# placa_carol.net
KiCad netlist of a schematic drawn in EAGLE
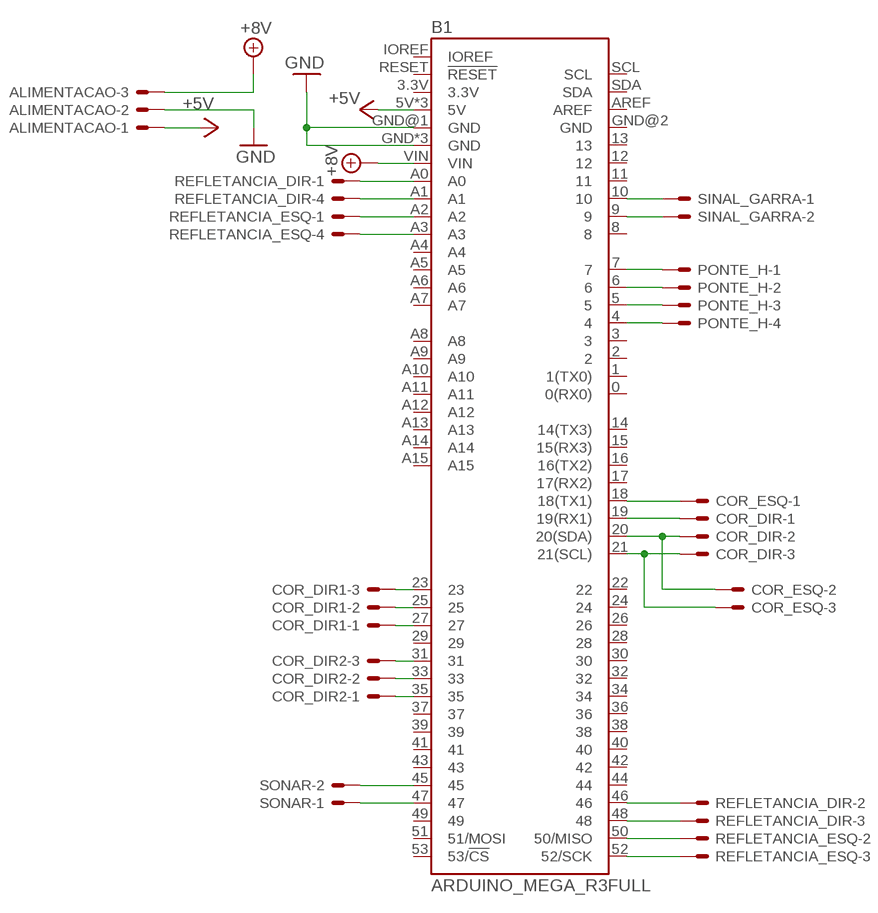
[diagram p0: schematic, sheet 1]

(export (version "E")
  (design (tool "Eeschema 10.0.6"))
  (components
    (comp (ref "ALIMENTACAO")
      (value "KK-156-3")
      (footprint "eagle-import:KK-156-3")
      (fields (field (name "MF") "MOLEX"))
      (libsource (lib "eagle-import") (part "KK-156-3"))
    )
    (comp (ref "B1")
      (value "ARDUINO_MEGA_R3FULL")
      (footprint "eagle-import:ARDUINO_MEGA_NO_SILK")
      (libsource (lib "eagle-import") (part "ARDUINO_MEGA_R3FULL"))
    )
    (comp (ref "COR_DIR")
      (value "JST-XH-03-PIN-LONG-PAD")
      (footprint "eagle-import:JST-XH-03-PACKAGE-LONG-PAD")
      (libsource (lib "eagle-import") (part "JST-XH-03-PIN-LONG-PAD"))
    )
    (comp (ref "COR_DIR1")
      (value "JST-XH-03-PIN-LONG-PAD")
      (footprint "eagle-import:JST-XH-03-PACKAGE-LONG-PAD")
      (libsource (lib "eagle-import") (part "JST-XH-03-PIN-LONG-PAD"))
    )
    (comp (ref "COR_DIR2")
      (value "JST-XH-03-PIN-LONG-PAD")
      (footprint "eagle-import:JST-XH-03-PACKAGE-LONG-PAD")
      (libsource (lib "eagle-import") (part "JST-XH-03-PIN-LONG-PAD"))
    )
    (comp (ref "COR_ESQ")
      (value "JST-XH-03-PIN-LONG-PAD")
      (footprint "eagle-import:JST-XH-03-PACKAGE-LONG-PAD")
      (libsource (lib "eagle-import") (part "JST-XH-03-PIN-LONG-PAD"))
    )
    (comp (ref "PONTE_H")
      (value "JST-XH-04-PIN-LONG-PAD")
      (footprint "eagle-import:JST-XH-04-PACKAGE-LONG-PAD")
      (libsource (lib "eagle-import") (part "JST-XH-04-PIN-LONG-PAD"))
    )
    (comp (ref "REFLETANCIA_DIR")
      (value "JST-XH-04-PIN-LONG-PAD")
      (footprint "eagle-import:JST-XH-04-PACKAGE-LONG-PAD")
      (libsource (lib "eagle-import") (part "JST-XH-04-PIN-LONG-PAD"))
    )
    (comp (ref "REFLETANCIA_ESQ")
      (value "JST-XH-04-PIN-LONG-PAD")
      (footprint "eagle-import:JST-XH-04-PACKAGE-LONG-PAD")
      (libsource (lib "eagle-import") (part "JST-XH-04-PIN-LONG-PAD"))
    )
    (comp (ref "SINAL_GARRA")
      (value "JST-XH-02-PIN-LONG-PAD")
      (footprint "eagle-import:JST-XH-02-PACKAGE-LONG-PAD")
      (libsource (lib "eagle-import") (part "JST-XH-02-PIN-LONG-PAD"))
    )
    (comp (ref "SONAR")
      (value "JST-XH-02-PIN-LONG-PAD")
      (footprint "eagle-import:JST-XH-02-PACKAGE-LONG-PAD")
      (libsource (lib "eagle-import") (part "JST-XH-02-PIN-LONG-PAD"))
    )
  )
  (nets
    (net (code "1") (name "+5V") (class "Default")
      (node (ref "ALIMENTACAO") (pin "1") (pinfunction "S_1") (pintype "passive"))
      (node (ref "B1") (pin "5V") (pinfunction "5V_5V") (pintype "bidirectional"))
      (node (ref "B1") (pin "5V@1") (pinfunction "5V_5V@1") (pintype "bidirectional"))
      (node (ref "B1") (pin "5V@2") (pinfunction "5V_5V@2") (pintype "bidirectional"))
    )
    (net (code "2") (name "+8V") (class "Default")
      (node (ref "ALIMENTACAO") (pin "3") (pinfunction "S_3") (pintype "passive"))
      (node (ref "B1") (pin "VIN") (pinfunction "VIN_VIN") (pintype "bidirectional"))
    )
    (net (code "3") (name "GND") (class "Default")
      (node (ref "ALIMENTACAO") (pin "2") (pinfunction "S_2") (pintype "passive"))
      (node (ref "B1") (pin "GND") (pinfunction "GND_GND") (pintype "bidirectional"))
      (node (ref "B1") (pin "GND@1") (pinfunction "GND_GND@1") (pintype "bidirectional"))
      (node (ref "B1") (pin "GND@3") (pinfunction "GND_GND@3") (pintype "bidirectional"))
      (node (ref "B1") (pin "GND@4") (pinfunction "GND_GND@4") (pintype "bidirectional"))
    )
    (net (code "4") (name "Net-(B1-18(TX1))") (class "Default")
      (node (ref "B1") (pin "18") (pinfunction "18(TX1)_18") (pintype "bidirectional"))
      (node (ref "COR_ESQ") (pin "1") (pinfunction "S_1") (pintype "passive"))
    )
    (net (code "5") (name "Net-(B1-19(RX1))") (class "Default")
      (node (ref "B1") (pin "19") (pinfunction "19(RX1)_19") (pintype "bidirectional"))
      (node (ref "COR_DIR") (pin "1") (pinfunction "S_1") (pintype "passive"))
    )
    (net (code "6") (name "Net-(B1-20(SDA))") (class "Default")
      (node (ref "B1") (pin "20") (pinfunction "20(SDA)_20") (pintype "bidirectional"))
      (node (ref "COR_DIR") (pin "2") (pinfunction "S_2") (pintype "passive"))
      (node (ref "COR_ESQ") (pin "2") (pinfunction "S_2") (pintype "passive"))
    )
    (net (code "7") (name "Net-(B1-21(SCL))") (class "Default")
      (node (ref "B1") (pin "21") (pinfunction "21(SCL)_21") (pintype "bidirectional"))
      (node (ref "COR_DIR") (pin "3") (pinfunction "S_3") (pintype "passive"))
      (node (ref "COR_ESQ") (pin "3") (pinfunction "S_3") (pintype "passive"))
    )
    (net (code "8") (name "Net-(B1-50{slash}MISO)") (class "Default")
      (node (ref "B1") (pin "50") (pinfunction "50/MISO_50") (pintype "bidirectional"))
      (node (ref "REFLETANCIA_ESQ") (pin "2") (pinfunction "S_2") (pintype "passive"))
    )
    (net (code "9") (name "Net-(B1-52{slash}SCK)") (class "Default")
      (node (ref "B1") (pin "52") (pinfunction "52/SCK_52") (pintype "bidirectional"))
      (node (ref "REFLETANCIA_ESQ") (pin "3") (pinfunction "S_3") (pintype "passive"))
    )
    (net (code "10") (name "Net-(COR_DIR1A-S)") (class "Default")
      (node (ref "B1") (pin "27") (pinfunction "27_27") (pintype "bidirectional"))
      (node (ref "COR_DIR1") (pin "1") (pinfunction "S_1") (pintype "passive"))
    )
    (net (code "11") (name "Net-(COR_DIR1B-S)") (class "Default")
      (node (ref "B1") (pin "25") (pinfunction "25_25") (pintype "bidirectional"))
      (node (ref "COR_DIR1") (pin "2") (pinfunction "S_2") (pintype "passive"))
    )
    (net (code "12") (name "Net-(COR_DIR1C-S)") (class "Default")
      (node (ref "B1") (pin "23") (pinfunction "23_23") (pintype "bidirectional"))
      (node (ref "COR_DIR1") (pin "3") (pinfunction "S_3") (pintype "passive"))
    )
    (net (code "13") (name "Net-(COR_DIR2A-S)") (class "Default")
      (node (ref "B1") (pin "35") (pinfunction "35_35") (pintype "bidirectional"))
      (node (ref "COR_DIR2") (pin "1") (pinfunction "S_1") (pintype "passive"))
    )
    (net (code "14") (name "Net-(COR_DIR2B-S)") (class "Default")
      (node (ref "B1") (pin "33") (pinfunction "33_33") (pintype "bidirectional"))
      (node (ref "COR_DIR2") (pin "2") (pinfunction "S_2") (pintype "passive"))
    )
    (net (code "15") (name "Net-(COR_DIR2C-S)") (class "Default")
      (node (ref "B1") (pin "31") (pinfunction "31_31") (pintype "bidirectional"))
      (node (ref "COR_DIR2") (pin "3") (pinfunction "S_3") (pintype "passive"))
    )
    (net (code "16") (name "Net-(PONTE_HA-S)") (class "Default")
      (node (ref "B1") (pin "7") (pinfunction "7_7") (pintype "bidirectional"))
      (node (ref "PONTE_H") (pin "1") (pinfunction "S_1") (pintype "passive"))
    )
    (net (code "17") (name "Net-(PONTE_HB-S)") (class "Default")
      (node (ref "B1") (pin "6") (pinfunction "6_6") (pintype "bidirectional"))
      (node (ref "PONTE_H") (pin "2") (pinfunction "S_2") (pintype "passive"))
    )
    (net (code "18") (name "Net-(PONTE_HC-S)") (class "Default")
      (node (ref "B1") (pin "5") (pinfunction "5_5") (pintype "bidirectional"))
      (node (ref "PONTE_H") (pin "3") (pinfunction "S_3") (pintype "passive"))
    )
    (net (code "19") (name "Net-(PONTE_HD-S)") (class "Default")
      (node (ref "B1") (pin "4") (pinfunction "4_4") (pintype "bidirectional"))
      (node (ref "PONTE_H") (pin "4") (pinfunction "S_4") (pintype "passive"))
    )
    (net (code "20") (name "Net-(REFLETANCIA_DIRA-S)") (class "Default")
      (node (ref "B1") (pin "A0") (pinfunction "A0_A0") (pintype "bidirectional"))
      (node (ref "REFLETANCIA_DIR") (pin "1") (pinfunction "S_1") (pintype "passive"))
    )
    (net (code "21") (name "Net-(REFLETANCIA_DIRB-S)") (class "Default")
      (node (ref "B1") (pin "46") (pinfunction "46_46") (pintype "bidirectional"))
      (node (ref "REFLETANCIA_DIR") (pin "2") (pinfunction "S_2") (pintype "passive"))
    )
    (net (code "22") (name "Net-(REFLETANCIA_DIRC-S)") (class "Default")
      (node (ref "B1") (pin "48") (pinfunction "48_48") (pintype "bidirectional"))
      (node (ref "REFLETANCIA_DIR") (pin "3") (pinfunction "S_3") (pintype "passive"))
    )
    (net (code "23") (name "Net-(REFLETANCIA_DIRD-S)") (class "Default")
      (node (ref "B1") (pin "A1") (pinfunction "A1_A1") (pintype "bidirectional"))
      (node (ref "REFLETANCIA_DIR") (pin "4") (pinfunction "S_4") (pintype "passive"))
    )
    (net (code "24") (name "Net-(REFLETANCIA_ESQA-S)") (class "Default")
      (node (ref "B1") (pin "A2") (pinfunction "A2_A2") (pintype "bidirectional"))
      (node (ref "REFLETANCIA_ESQ") (pin "1") (pinfunction "S_1") (pintype "passive"))
    )
    (net (code "25") (name "Net-(REFLETANCIA_ESQD-S)") (class "Default")
      (node (ref "B1") (pin "A3") (pinfunction "A3_A3") (pintype "bidirectional"))
      (node (ref "REFLETANCIA_ESQ") (pin "4") (pinfunction "S_4") (pintype "passive"))
    )
    (net (code "26") (name "Net-(SINAL_GARRAA-S)") (class "Default")
      (node (ref "B1") (pin "10") (pinfunction "10_10") (pintype "bidirectional"))
      (node (ref "SINAL_GARRA") (pin "1") (pinfunction "S_1") (pintype "passive"))
    )
    (net (code "27") (name "Net-(SINAL_GARRAB-S)") (class "Default")
      (node (ref "B1") (pin "9") (pinfunction "9_9") (pintype "bidirectional"))
      (node (ref "SINAL_GARRA") (pin "2") (pinfunction "S_2") (pintype "passive"))
    )
    (net (code "28") (name "Net-(SONARA-S)") (class "Default")
      (node (ref "B1") (pin "47") (pinfunction "47_47") (pintype "bidirectional"))
      (node (ref "SONAR") (pin "1") (pinfunction "S_1") (pintype "passive"))
    )
    (net (code "29") (name "Net-(SONARB-S)") (class "Default")
      (node (ref "B1") (pin "45") (pinfunction "45_45") (pintype "bidirectional"))
      (node (ref "SONAR") (pin "2") (pinfunction "S_2") (pintype "passive"))
    )
    (net (code "30") (name "unconnected-(B1-0(RX0)-Pad0)") (class "Default")
      (node (ref "B1") (pin "0") (pinfunction "0(RX0)_0") (pintype "bidirectional"))
    )
    (net (code "31") (name "unconnected-(B1-1(TX0)-Pad1)") (class "Default")
      (node (ref "B1") (pin "1") (pinfunction "1(TX0)_1") (pintype "bidirectional"))
    )
    (net (code "32") (name "unconnected-(B1-14(TX3)-Pad14)") (class "Default")
      (node (ref "B1") (pin "14") (pinfunction "14(TX3)_14") (pintype "bidirectional"))
    )
    (net (code "33") (name "unconnected-(B1-15(RX3)-Pad15)") (class "Default")
      (node (ref "B1") (pin "15") (pinfunction "15(RX3)_15") (pintype "bidirectional"))
    )
    (net (code "34") (name "unconnected-(B1-16(TX2)-Pad16)") (class "Default")
      (node (ref "B1") (pin "16") (pinfunction "16(TX2)_16") (pintype "bidirectional"))
    )
    (net (code "35") (name "unconnected-(B1-17(RX2)-Pad17)") (class "Default")
      (node (ref "B1") (pin "17") (pinfunction "17(RX2)_17") (pintype "bidirectional"))
    )
    (net (code "36") (name "unconnected-(B1-51{slash}MOSI-Pad51)") (class "Default")
      (node (ref "B1") (pin "51") (pinfunction "51/MOSI_51") (pintype "bidirectional"))
    )
    (net (code "37") (name "unconnected-(B1-53{slash}~{CS}-Pad53)") (class "Default")
      (node (ref "B1") (pin "53") (pinfunction "53/~{CS}_53") (pintype "bidirectional"))
    )
    (net (code "38") (name "unconnected-(B1-GND-PadGND@2)") (class "Default")
      (node (ref "B1") (pin "GND@2") (pinfunction "GND_GND@2") (pintype "bidirectional"))
    )
    (net (code "39") (name "unconnected-(B1-Pad2)") (class "Default")
      (node (ref "B1") (pin "2") (pinfunction "2_2") (pintype "bidirectional"))
    )
    (net (code "40") (name "unconnected-(B1-Pad3)") (class "Default")
      (node (ref "B1") (pin "3") (pinfunction "3_3") (pintype "bidirectional"))
    )
    (net (code "41") (name "unconnected-(B1-Pad3.3V)") (class "Default")
      (node (ref "B1") (pin "3.3V") (pinfunction "3.3V_3.3V") (pintype "bidirectional"))
    )
    (net (code "42") (name "unconnected-(B1-Pad8)") (class "Default")
      (node (ref "B1") (pin "8") (pinfunction "8_8") (pintype "bidirectional"))
    )
    (net (code "43") (name "unconnected-(B1-Pad11)") (class "Default")
      (node (ref "B1") (pin "11") (pinfunction "11_11") (pintype "bidirectional"))
    )
    (net (code "44") (name "unconnected-(B1-Pad12)") (class "Default")
      (node (ref "B1") (pin "12") (pinfunction "12_12") (pintype "bidirectional"))
    )
    (net (code "45") (name "unconnected-(B1-Pad13)") (class "Default")
      (node (ref "B1") (pin "13") (pinfunction "13_13") (pintype "bidirectional"))
    )
    (net (code "46") (name "unconnected-(B1-Pad22)") (class "Default")
      (node (ref "B1") (pin "22") (pinfunction "22_22") (pintype "bidirectional"))
    )
    (net (code "47") (name "unconnected-(B1-Pad24)") (class "Default")
      (node (ref "B1") (pin "24") (pinfunction "24_24") (pintype "bidirectional"))
    )
    (net (code "48") (name "unconnected-(B1-Pad26)") (class "Default")
      (node (ref "B1") (pin "26") (pinfunction "26_26") (pintype "bidirectional"))
    )
    (net (code "49") (name "unconnected-(B1-Pad28)") (class "Default")
      (node (ref "B1") (pin "28") (pinfunction "28_28") (pintype "bidirectional"))
    )
    (net (code "50") (name "unconnected-(B1-Pad29)") (class "Default")
      (node (ref "B1") (pin "29") (pinfunction "29_29") (pintype "bidirectional"))
    )
    (net (code "51") (name "unconnected-(B1-Pad30)") (class "Default")
      (node (ref "B1") (pin "30") (pinfunction "30_30") (pintype "bidirectional"))
    )
    (net (code "52") (name "unconnected-(B1-Pad32)") (class "Default")
      (node (ref "B1") (pin "32") (pinfunction "32_32") (pintype "bidirectional"))
    )
    (net (code "53") (name "unconnected-(B1-Pad34)") (class "Default")
      (node (ref "B1") (pin "34") (pinfunction "34_34") (pintype "bidirectional"))
    )
    (net (code "54") (name "unconnected-(B1-Pad36)") (class "Default")
      (node (ref "B1") (pin "36") (pinfunction "36_36") (pintype "bidirectional"))
    )
    (net (code "55") (name "unconnected-(B1-Pad37)") (class "Default")
      (node (ref "B1") (pin "37") (pinfunction "37_37") (pintype "bidirectional"))
    )
    (net (code "56") (name "unconnected-(B1-Pad38)") (class "Default")
      (node (ref "B1") (pin "38") (pinfunction "38_38") (pintype "bidirectional"))
    )
    (net (code "57") (name "unconnected-(B1-Pad39)") (class "Default")
      (node (ref "B1") (pin "39") (pinfunction "39_39") (pintype "bidirectional"))
    )
    (net (code "58") (name "unconnected-(B1-Pad40)") (class "Default")
      (node (ref "B1") (pin "40") (pinfunction "40_40") (pintype "bidirectional"))
    )
    (net (code "59") (name "unconnected-(B1-Pad41)") (class "Default")
      (node (ref "B1") (pin "41") (pinfunction "41_41") (pintype "bidirectional"))
    )
    (net (code "60") (name "unconnected-(B1-Pad42)") (class "Default")
      (node (ref "B1") (pin "42") (pinfunction "42_42") (pintype "bidirectional"))
    )
    (net (code "61") (name "unconnected-(B1-Pad43)") (class "Default")
      (node (ref "B1") (pin "43") (pinfunction "43_43") (pintype "bidirectional"))
    )
    (net (code "62") (name "unconnected-(B1-Pad44)") (class "Default")
      (node (ref "B1") (pin "44") (pinfunction "44_44") (pintype "bidirectional"))
    )
    (net (code "63") (name "unconnected-(B1-Pad49)") (class "Default")
      (node (ref "B1") (pin "49") (pinfunction "49_49") (pintype "bidirectional"))
    )
    (net (code "64") (name "unconnected-(B1-PadA4)") (class "Default")
      (node (ref "B1") (pin "A4") (pinfunction "A4_A4") (pintype "bidirectional"))
    )
    (net (code "65") (name "unconnected-(B1-PadA5)") (class "Default")
      (node (ref "B1") (pin "A5") (pinfunction "A5_A5") (pintype "bidirectional"))
    )
    (net (code "66") (name "unconnected-(B1-PadA6)") (class "Default")
      (node (ref "B1") (pin "A6") (pinfunction "A6_A6") (pintype "bidirectional"))
    )
    (net (code "67") (name "unconnected-(B1-PadA7)") (class "Default")
      (node (ref "B1") (pin "A7") (pinfunction "A7_A7") (pintype "bidirectional"))
    )
    (net (code "68") (name "unconnected-(B1-PadA8)") (class "Default")
      (node (ref "B1") (pin "A8") (pinfunction "A8_A8") (pintype "bidirectional"))
    )
    (net (code "69") (name "unconnected-(B1-PadA9)") (class "Default")
      (node (ref "B1") (pin "A9") (pinfunction "A9_A9") (pintype "bidirectional"))
    )
    (net (code "70") (name "unconnected-(B1-PadA10)") (class "Default")
      (node (ref "B1") (pin "A10") (pinfunction "A10_A10") (pintype "bidirectional"))
    )
    (net (code "71") (name "unconnected-(B1-PadA11)") (class "Default")
      (node (ref "B1") (pin "A11") (pinfunction "A11_A11") (pintype "bidirectional"))
    )
    (net (code "72") (name "unconnected-(B1-PadA12)") (class "Default")
      (node (ref "B1") (pin "A12") (pinfunction "A12_A12") (pintype "bidirectional"))
    )
    (net (code "73") (name "unconnected-(B1-PadA13)") (class "Default")
      (node (ref "B1") (pin "A13") (pinfunction "A13_A13") (pintype "bidirectional"))
    )
    (net (code "74") (name "unconnected-(B1-PadA14)") (class "Default")
      (node (ref "B1") (pin "A14") (pinfunction "A14_A14") (pintype "bidirectional"))
    )
    (net (code "75") (name "unconnected-(B1-PadA15)") (class "Default")
      (node (ref "B1") (pin "A15") (pinfunction "A15_A15") (pintype "bidirectional"))
    )
    (net (code "76") (name "unconnected-(B1-PadAREF)") (class "Default")
      (node (ref "B1") (pin "AREF") (pinfunction "AREF_AREF") (pintype "bidirectional"))
    )
    (net (code "77") (name "unconnected-(B1-PadIOREF)") (class "Default")
      (node (ref "B1") (pin "IOREF") (pinfunction "IOREF_IOREF") (pintype "bidirectional"))
    )
    (net (code "78") (name "unconnected-(B1-PadSCL)") (class "Default")
      (node (ref "B1") (pin "SCL") (pinfunction "SCL_SCL") (pintype "bidirectional"))
    )
    (net (code "79") (name "unconnected-(B1-PadSDA)") (class "Default")
      (node (ref "B1") (pin "SDA") (pinfunction "SDA_SDA") (pintype "bidirectional"))
    )
    (net (code "80") (name "unconnected-(B1-~{RESET}-PadRESET)") (class "Default")
      (node (ref "B1") (pin "RESET") (pinfunction "~{RESET}_RESET") (pintype "bidirectional"))
    )
  )
)
